# LedBlinker_End.net
KiCad netlist of a schematic drawn in Altium Designer
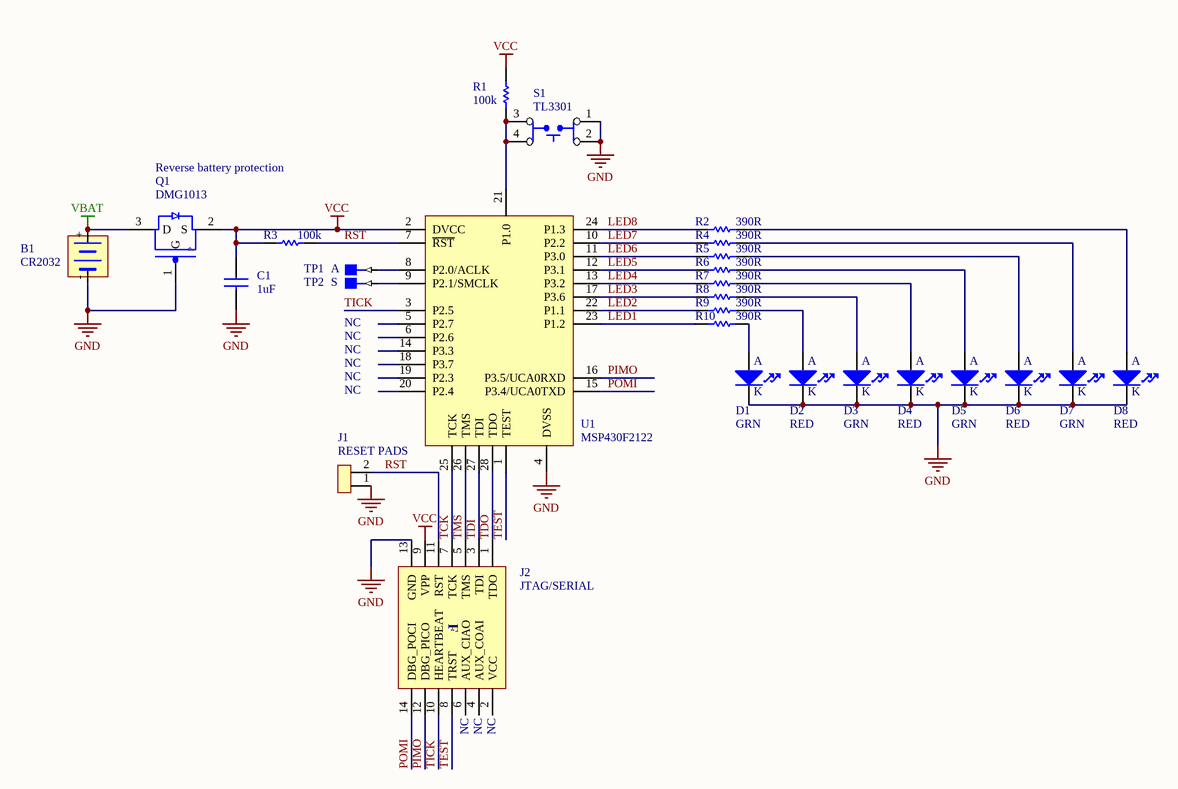
[diagram p0: LedBlinker End.SchDoc]

(export (version "E")
  (design (tool "Eeschema 10.0.6"))
  (components
    (comp (ref "B1")
      (value "CR2032")
      (footprint "CONN BATTERY HOLDER CR2032")
      (description "3V Coincell Battery")
      (fields
        (field (name "3. MANUFACTURER PART NUMBER") "BK-912")
        (field (name "4. DIGI-KEY PART NUMBER") "BK-912-ND")
        (field (name "7. MODIFIED BY") "JRL")
      )
      (libsource (lib "Altium Example Master Schematic Library End") (part "CONN BATTERY HOLDER CR2032"))
    )
    (comp (ref "C1")
      (value "1uF")
      (footprint "0603")
      (fields
        (field (name "5. INTERNAL PART NUMBER") "100009")
        (field (name "4. DIGI-KEY PART NUMBER") "587-1251-2-ND")
        (field (name "3. MANUFACTURER PART NUMBER") "EMK107BJ105KA-T")
        (field (name "7. MODIFIED BY") "JRL")
      )
      (libsource (lib "Altium Example Master Schematic Library End") (part "CAPACITOR NON-POLARIZED"))
    )
    (comp (ref "D1")
      (value "GRN")
      (footprint "PLCC-2 AK")
      (fields
        (field (name "3. MANUFACTURER PART NUMBER") "AA3528CGSK")
        (field (name "4. DIGI-KEY PART NUMBER") "754-1528-2-ND")
        (field (name "5. INTERNAL PART NUMBER") "100110")
        (field (name "7. MODIFIED BY") "JRL")
      )
      (libsource (lib "Altium Example Master Schematic Library End") (part "LED AK"))
    )
    (comp (ref "D2")
      (value "RED")
      (footprint "PLCC-2 AK")
      (fields
        (field (name "3. MANUFACTURER PART NUMBER") "AA3528SURSK")
        (field (name "4. DIGI-KEY PART NUMBER") "754-1537-2-ND")
        (field (name "5. INTERNAL PART NUMBER") "100113")
        (field (name "7. MODIFIED BY") "JRL")
      )
      (libsource (lib "Altium Example Master Schematic Library End") (part "LED AK"))
    )
    (comp (ref "D3")
      (value "GRN")
      (footprint "PLCC-2 AK")
      (fields
        (field (name "3. MANUFACTURER PART NUMBER") "AA3528CGSK")
        (field (name "4. DIGI-KEY PART NUMBER") "754-1528-2-ND")
        (field (name "5. INTERNAL PART NUMBER") "100110")
        (field (name "7. MODIFIED BY") "JRL")
      )
      (libsource (lib "Altium Example Master Schematic Library End") (part "LED AK"))
    )
    (comp (ref "D4")
      (value "RED")
      (footprint "PLCC-2 AK")
      (fields
        (field (name "3. MANUFACTURER PART NUMBER") "AA3528SURSK")
        (field (name "4. DIGI-KEY PART NUMBER") "754-1537-2-ND")
        (field (name "5. INTERNAL PART NUMBER") "100113")
        (field (name "7. MODIFIED BY") "JRL")
      )
      (libsource (lib "Altium Example Master Schematic Library End") (part "LED AK"))
    )
    (comp (ref "D5")
      (value "GRN")
      (footprint "PLCC-2 AK")
      (fields
        (field (name "3. MANUFACTURER PART NUMBER") "AA3528CGSK")
        (field (name "4. DIGI-KEY PART NUMBER") "754-1528-2-ND")
        (field (name "5. INTERNAL PART NUMBER") "100110")
        (field (name "7. MODIFIED BY") "JRL")
      )
      (libsource (lib "Altium Example Master Schematic Library End") (part "LED AK"))
    )
    (comp (ref "D6")
      (value "RED")
      (footprint "PLCC-2 AK")
      (fields
        (field (name "3. MANUFACTURER PART NUMBER") "AA3528SURSK")
        (field (name "4. DIGI-KEY PART NUMBER") "754-1537-2-ND")
        (field (name "5. INTERNAL PART NUMBER") "100113")
        (field (name "7. MODIFIED BY") "JRL")
      )
      (libsource (lib "Altium Example Master Schematic Library End") (part "LED AK"))
    )
    (comp (ref "D7")
      (value "GRN")
      (footprint "PLCC-2 AK")
      (fields
        (field (name "3. MANUFACTURER PART NUMBER") "AA3528CGSK")
        (field (name "4. DIGI-KEY PART NUMBER") "754-1528-2-ND")
        (field (name "5. INTERNAL PART NUMBER") "100110")
        (field (name "7. MODIFIED BY") "JRL")
      )
      (libsource (lib "Altium Example Master Schematic Library End") (part "LED AK"))
    )
    (comp (ref "D8")
      (value "RED")
      (footprint "PLCC-2 AK")
      (fields
        (field (name "3. MANUFACTURER PART NUMBER") "AA3528SURSK")
        (field (name "4. DIGI-KEY PART NUMBER") "754-1537-2-ND")
        (field (name "5. INTERNAL PART NUMBER") "100113")
        (field (name "7. MODIFIED BY") "JRL")
      )
      (libsource (lib "Altium Example Master Schematic Library End") (part "LED AK"))
    )
    (comp (ref "J1")
      (value "RESET PADS")
      (footprint "JUMPER POINTS")
      (fields (field (name "7. MODIFIED BY") "*"))
      (libsource (lib "Altium Example Master Schematic Library End") (part "CONN SIP 2"))
    )
    (comp (ref "J2")
      (value "JTAG/SERIAL")
      (footprint "CONN 14POS 7X2 SMT FEMALE SMALL")
      (fields
        (field (name "3. MANUFACTURER PART NUMBER") "20021321-00014T4LF")
        (field (name "4. DIGI-KEY PART NUMBER") "609-3771-ND")
        (field (name "5. INTERNAL PART NUMBER") "100254")
        (field (name "7. MODIFIED BY") "JRL")
      )
      (libsource (lib "Engenuics Master Schematic Library") (part "CONN JTAG/SERIAL DEBUG 14POS FEMALE"))
    )
    (comp (ref "Q1")
      (value "DMG1013")
      (footprint "SC-70-3")
      (fields
        (field (name "3. MANUFACTURER PART NUMBER") "DMG1013UW-7")
        (field (name "4. DIGI-KEY PART NUMBER") "DMG1013UW-7DICT-ND")
        (field (name "5. INTERNAL PART NUMBER") "100279")
        (field (name "7. MODIFIED BY") "JRL")
      )
      (libsource (lib "Altium Example Master Schematic Library End") (part "TRANS PMOS 1G 2S 3D"))
    )
    (comp (ref "R1")
      (value "100k")
      (footprint "0603")
      (fields
        (field (name "5. INTERNAL PART NUMBER") "100078")
        (field (name "4. DIGI-KEY PART NUMBER") "311-100KHRTR-ND")
        (field (name "3. MANUFACTURER PART NUMBER") "RC0603FR-07100KL")
        (field (name "7. MODIFIED BY") "JRL")
      )
      (libsource (lib "Altium Example Master Schematic Library End") (part "RESISTOR"))
    )
    (comp (ref "R2")
      (value "390R")
      (footprint "0603")
      (fields
        (field (name "5. INTERNAL PART NUMBER") "100098")
        (field (name "4. DIGI-KEY PART NUMBER") "311-390HRTR-ND")
        (field (name "3. MANUFACTURER PART NUMBER") "RC0603FR-07390RL")
        (field (name "7. MODIFIED BY") "JRL")
      )
      (libsource (lib "Altium Example Master Schematic Library End") (part "RESISTOR"))
    )
    (comp (ref "R3")
      (value "100k")
      (footprint "0603")
      (fields
        (field (name "5. INTERNAL PART NUMBER") "100078")
        (field (name "4. DIGI-KEY PART NUMBER") "311-100KHRTR-ND")
        (field (name "3. MANUFACTURER PART NUMBER") "RC0603FR-07100KL")
        (field (name "7. MODIFIED BY") "JRL")
      )
      (libsource (lib "Altium Example Master Schematic Library End") (part "RESISTOR"))
    )
    (comp (ref "R4")
      (value "390R")
      (footprint "0603")
      (fields
        (field (name "5. INTERNAL PART NUMBER") "100098")
        (field (name "4. DIGI-KEY PART NUMBER") "311-390HRTR-ND")
        (field (name "3. MANUFACTURER PART NUMBER") "RC0603FR-07390RL")
        (field (name "7. MODIFIED BY") "JRL")
      )
      (libsource (lib "Altium Example Master Schematic Library End") (part "RESISTOR"))
    )
    (comp (ref "R5")
      (value "390R")
      (footprint "0603")
      (fields
        (field (name "5. INTERNAL PART NUMBER") "100098")
        (field (name "4. DIGI-KEY PART NUMBER") "311-390HRTR-ND")
        (field (name "3. MANUFACTURER PART NUMBER") "RC0603FR-07390RL")
        (field (name "7. MODIFIED BY") "JRL")
      )
      (libsource (lib "Altium Example Master Schematic Library End") (part "RESISTOR"))
    )
    (comp (ref "R6")
      (value "390R")
      (footprint "0603")
      (fields
        (field (name "5. INTERNAL PART NUMBER") "100098")
        (field (name "4. DIGI-KEY PART NUMBER") "311-390HRTR-ND")
        (field (name "3. MANUFACTURER PART NUMBER") "RC0603FR-07390RL")
        (field (name "7. MODIFIED BY") "JRL")
      )
      (libsource (lib "Altium Example Master Schematic Library End") (part "RESISTOR"))
    )
    (comp (ref "R7")
      (value "390R")
      (footprint "0603")
      (fields
        (field (name "5. INTERNAL PART NUMBER") "100098")
        (field (name "4. DIGI-KEY PART NUMBER") "311-390HRTR-ND")
        (field (name "3. MANUFACTURER PART NUMBER") "RC0603FR-07390RL")
        (field (name "7. MODIFIED BY") "JRL")
      )
      (libsource (lib "Altium Example Master Schematic Library End") (part "RESISTOR"))
    )
    (comp (ref "R8")
      (value "390R")
      (footprint "0603")
      (fields
        (field (name "5. INTERNAL PART NUMBER") "100098")
        (field (name "4. DIGI-KEY PART NUMBER") "311-390HRTR-ND")
        (field (name "3. MANUFACTURER PART NUMBER") "RC0603FR-07390RL")
        (field (name "7. MODIFIED BY") "JRL")
      )
      (libsource (lib "Altium Example Master Schematic Library End") (part "RESISTOR"))
    )
    (comp (ref "R9")
      (value "390R")
      (footprint "0603")
      (fields
        (field (name "5. INTERNAL PART NUMBER") "100098")
        (field (name "4. DIGI-KEY PART NUMBER") "311-390HRTR-ND")
        (field (name "3. MANUFACTURER PART NUMBER") "RC0603FR-07390RL")
        (field (name "7. MODIFIED BY") "JRL")
      )
      (libsource (lib "Altium Example Master Schematic Library End") (part "RESISTOR"))
    )
    (comp (ref "R10")
      (value "390R")
      (footprint "0603")
      (fields
        (field (name "5. INTERNAL PART NUMBER") "100098")
        (field (name "4. DIGI-KEY PART NUMBER") "311-390HRTR-ND")
        (field (name "3. MANUFACTURER PART NUMBER") "RC0603FR-07390RL")
        (field (name "7. MODIFIED BY") "JRL")
      )
      (libsource (lib "Altium Example Master Schematic Library End") (part "RESISTOR"))
    )
    (comp (ref "S1")
      (value "TL3301")
      (footprint "SWITCH TACT SMT TL3301 J LEAD")
      (description "SPST TACT SWITCH")
      (fields
        (field (name "3. MANUFACTURER PART NUMBER") "TL3301AF160QJ")
        (field (name "4. DIGI-KEY PART NUMBER") "EG4374TR-ND")
        (field (name "7. MODIFIED BY") "JRL")
      )
      (libsource (lib "Engenuics Master Schematic Library") (part "SWITCH SPST TL3301 JLEAD"))
    )
    (comp (ref "TP1")
      (value "A")
      (footprint "TEST POINT SMT TINY")
      (fields (field (name "7. MODIFIED BY") "JRL"))
      (libsource (lib "Engenuics Master Schematic Library") (part "TEST POINT SMT"))
    )
    (comp (ref "TP2")
      (value "S")
      (footprint "TEST POINT SMT TINY")
      (fields (field (name "7. MODIFIED BY") "JRL"))
      (libsource (lib "Engenuics Master Schematic Library") (part "TEST POINT SMT"))
    )
    (comp (ref "U1")
      (value "MSP430F2122")
      (footprint "TSSOP28")
      (fields
        (field (name "3. MANUFACTURER PART NUMBER") "MSP430F2122IIPW")
        (field (name "4. DIGI-KEY PART NUMBER") "296-23363-2-ND")
        (field (name "5. INTERNAL PART NUMBER") "100207")
        (field (name "7. MODIFIED BY") "JRL")
      )
      (libsource (lib "Altium Example Master Schematic Library End") (part "MCU MSP430F2122 TSSOP28 LED BLINKER"))
    )
  )
  (nets
    (net (code "1") (name "/LED1") (class "Default")
      (node (ref "R10") (pin "1") (pinfunction "1_1") (pintype "passive"))
      (node (ref "U1") (pin "23") (pinfunction "P1.2_23") (pintype "passive"))
    )
    (net (code "2") (name "/LED2") (class "Default")
      (node (ref "R9") (pin "1") (pinfunction "1_1") (pintype "passive"))
      (node (ref "U1") (pin "22") (pinfunction "P1.1_22") (pintype "passive"))
    )
    (net (code "3") (name "/LED3") (class "Default")
      (node (ref "R8") (pin "1") (pinfunction "1_1") (pintype "passive"))
      (node (ref "U1") (pin "17") (pinfunction "P3.6_17") (pintype "passive"))
    )
    (net (code "4") (name "/LED4") (class "Default")
      (node (ref "R7") (pin "1") (pinfunction "1_1") (pintype "passive"))
      (node (ref "U1") (pin "13") (pinfunction "P3.2_13") (pintype "passive"))
    )
    (net (code "5") (name "/LED5") (class "Default")
      (node (ref "R6") (pin "1") (pinfunction "1_1") (pintype "passive"))
      (node (ref "U1") (pin "12") (pinfunction "P3.1_12") (pintype "passive"))
    )
    (net (code "6") (name "/LED6") (class "Default")
      (node (ref "R5") (pin "1") (pinfunction "1_1") (pintype "passive"))
      (node (ref "U1") (pin "11") (pinfunction "P3.0_11") (pintype "passive"))
    )
    (net (code "7") (name "/LED7") (class "Default")
      (node (ref "R4") (pin "1") (pinfunction "1_1") (pintype "passive"))
      (node (ref "U1") (pin "10") (pinfunction "P2.2_10") (pintype "passive"))
    )
    (net (code "8") (name "/LED8") (class "Default")
      (node (ref "R2") (pin "1") (pinfunction "1_1") (pintype "passive"))
      (node (ref "U1") (pin "24") (pinfunction "P1.3_24") (pintype "passive"))
    )
    (net (code "9") (name "/PIMO") (class "Default")
      (node (ref "J2") (pin "12") (pinfunction "DBG_PICO_12") (pintype "passive"))
      (node (ref "U1") (pin "16") (pinfunction "P3.5/UCA0RXD_16") (pintype "passive"))
    )
    (net (code "10") (name "/POMI") (class "Default")
      (node (ref "J2") (pin "14") (pinfunction "DBG_POCI_14") (pintype "passive"))
      (node (ref "U1") (pin "15") (pinfunction "P3.4/UCA0TXD_15") (pintype "passive"))
    )
    (net (code "11") (name "/RST") (class "Default")
      (node (ref "J1") (pin "2") (pintype "passive"))
      (node (ref "J2") (pin "11") (pinfunction "RST_11") (pintype "passive"))
      (node (ref "R3") (pin "1") (pinfunction "1_1") (pintype "passive"))
      (node (ref "U1") (pin "7") (pinfunction "~{RST}_7") (pintype "passive"))
    )
    (net (code "12") (name "/TCK") (class "Default")
      (node (ref "J2") (pin "7") (pinfunction "TCK_7") (pintype "passive"))
      (node (ref "U1") (pin "25") (pinfunction "TCK_25") (pintype "passive"))
    )
    (net (code "13") (name "/TDI") (class "Default")
      (node (ref "J2") (pin "3") (pinfunction "TDI_3") (pintype "passive"))
      (node (ref "U1") (pin "27") (pinfunction "TDI_27") (pintype "passive"))
    )
    (net (code "14") (name "/TDO") (class "Default")
      (node (ref "J2") (pin "1") (pinfunction "TDO_1") (pintype "passive"))
      (node (ref "U1") (pin "28") (pinfunction "TDO_28") (pintype "passive"))
    )
    (net (code "15") (name "/TEST") (class "Default")
      (node (ref "J2") (pin "8") (pinfunction "TRST_8") (pintype "passive"))
      (node (ref "U1") (pin "1") (pinfunction "TEST_1") (pintype "passive"))
    )
    (net (code "16") (name "/TICK") (class "Default")
      (node (ref "J2") (pin "10") (pinfunction "HEARTBEAT_10") (pintype "passive"))
      (node (ref "U1") (pin "3") (pinfunction "P2.5_3") (pintype "passive"))
    )
    (net (code "17") (name "/TMS") (class "Default")
      (node (ref "J2") (pin "5") (pinfunction "TMS_5") (pintype "passive"))
      (node (ref "U1") (pin "26") (pinfunction "TMS_26") (pintype "passive"))
    )
    (net (code "18") (name "GND") (class "Default")
      (node (ref "B1") (pin "-") (pintype "passive"))
      (node (ref "C1") (pin "2") (pinfunction "2_2") (pintype "passive"))
      (node (ref "D1") (pin "K") (pinfunction "K_K") (pintype "passive"))
      (node (ref "D2") (pin "K") (pinfunction "K_K") (pintype "passive"))
      (node (ref "D3") (pin "K") (pinfunction "K_K") (pintype "passive"))
      (node (ref "D4") (pin "K") (pinfunction "K_K") (pintype "passive"))
      (node (ref "D5") (pin "K") (pinfunction "K_K") (pintype "passive"))
      (node (ref "D6") (pin "K") (pinfunction "K_K") (pintype "passive"))
      (node (ref "D7") (pin "K") (pinfunction "K_K") (pintype "passive"))
      (node (ref "D8") (pin "K") (pinfunction "K_K") (pintype "passive"))
      (node (ref "J1") (pin "1") (pintype "passive"))
      (node (ref "J2") (pin "13") (pinfunction "GND_13") (pintype "power_in"))
      (node (ref "Q1") (pin "1") (pinfunction "G_1") (pintype "passive"))
      (node (ref "S1") (pin "1") (pinfunction "X1_1") (pintype "passive"))
      (node (ref "S1") (pin "2") (pinfunction "X2_2") (pintype "passive"))
      (node (ref "U1") (pin "4") (pinfunction "DVSS_4") (pintype "passive"))
    )
    (net (code "19") (name "Net-(D1-PadA)") (class "Default")
      (node (ref "D1") (pin "A") (pinfunction "A_A") (pintype "passive"))
      (node (ref "R10") (pin "2") (pinfunction "2_2") (pintype "passive"))
    )
    (net (code "20") (name "Net-(D2-PadA)") (class "Default")
      (node (ref "D2") (pin "A") (pinfunction "A_A") (pintype "passive"))
      (node (ref "R9") (pin "2") (pinfunction "2_2") (pintype "passive"))
    )
    (net (code "21") (name "Net-(D3-PadA)") (class "Default")
      (node (ref "D3") (pin "A") (pinfunction "A_A") (pintype "passive"))
      (node (ref "R8") (pin "2") (pinfunction "2_2") (pintype "passive"))
    )
    (net (code "22") (name "Net-(D4-PadA)") (class "Default")
      (node (ref "D4") (pin "A") (pinfunction "A_A") (pintype "passive"))
      (node (ref "R7") (pin "2") (pinfunction "2_2") (pintype "passive"))
    )
    (net (code "23") (name "Net-(D5-PadA)") (class "Default")
      (node (ref "D5") (pin "A") (pinfunction "A_A") (pintype "passive"))
      (node (ref "R6") (pin "2") (pinfunction "2_2") (pintype "passive"))
    )
    (net (code "24") (name "Net-(D6-PadA)") (class "Default")
      (node (ref "D6") (pin "A") (pinfunction "A_A") (pintype "passive"))
      (node (ref "R5") (pin "2") (pinfunction "2_2") (pintype "passive"))
    )
    (net (code "25") (name "Net-(D7-PadA)") (class "Default")
      (node (ref "D7") (pin "A") (pinfunction "A_A") (pintype "passive"))
      (node (ref "R4") (pin "2") (pinfunction "2_2") (pintype "passive"))
    )
    (net (code "26") (name "Net-(D8-PadA)") (class "Default")
      (node (ref "D8") (pin "A") (pinfunction "A_A") (pintype "passive"))
      (node (ref "R2") (pin "2") (pinfunction "2_2") (pintype "passive"))
    )
    (net (code "27") (name "Net-(S1-Y1)") (class "Default")
      (node (ref "R1") (pin "1") (pinfunction "1_1") (pintype "passive"))
      (node (ref "S1") (pin "3") (pinfunction "Y1_3") (pintype "passive"))
      (node (ref "S1") (pin "4") (pinfunction "Y2_4") (pintype "passive"))
      (node (ref "U1") (pin "21") (pinfunction "P1.0_21") (pintype "passive"))
    )
    (net (code "28") (name "Net-(U1-P2.0{slash}ACLK)") (class "Default")
      (node (ref "TP1") (pin "1") (pinfunction "1_1") (pintype "input"))
      (node (ref "U1") (pin "8") (pinfunction "P2.0/ACLK_8") (pintype "passive"))
    )
    (net (code "29") (name "Net-(U1-P2.1{slash}SMCLK)") (class "Default")
      (node (ref "TP2") (pin "1") (pinfunction "1_1") (pintype "input"))
      (node (ref "U1") (pin "9") (pinfunction "P2.1/SMCLK_9") (pintype "passive"))
    )
    (net (code "30") (name "VBAT") (class "Default")
      (node (ref "B1") (pin "+") (pintype "passive"))
      (node (ref "Q1") (pin "3") (pinfunction "D_3") (pintype "passive"))
    )
    (net (code "31") (name "VCC") (class "Default")
      (node (ref "C1") (pin "1") (pinfunction "1_1") (pintype "passive"))
      (node (ref "J2") (pin "9") (pinfunction "VPP_9") (pintype "passive"))
      (node (ref "Q1") (pin "2") (pinfunction "S_2") (pintype "passive"))
      (node (ref "R1") (pin "2") (pinfunction "2_2") (pintype "passive"))
      (node (ref "R3") (pin "2") (pinfunction "2_2") (pintype "passive"))
      (node (ref "U1") (pin "2") (pinfunction "DVCC_2") (pintype "passive"))
    )
    (net (code "32") (name "unconnected-(J2-AUX_CIAO-Pad6)") (class "Default")
      (node (ref "J2") (pin "6") (pinfunction "AUX_CIAO_6") (pintype "passive"))
    )
    (net (code "33") (name "unconnected-(J2-AUX_COAI-Pad4)") (class "Default")
      (node (ref "J2") (pin "4") (pinfunction "AUX_COAI_4") (pintype "passive"))
    )
    (net (code "34") (name "unconnected-(J2-VCC-Pad2)") (class "Default")
      (node (ref "J2") (pin "2") (pinfunction "VCC_2") (pintype "passive"))
    )
    (net (code "35") (name "unconnected-(U1-P2.3-Pad19)") (class "Default")
      (node (ref "U1") (pin "19") (pinfunction "P2.3_19") (pintype "passive"))
    )
    (net (code "36") (name "unconnected-(U1-P2.4-Pad20)") (class "Default")
      (node (ref "U1") (pin "20") (pinfunction "P2.4_20") (pintype "passive"))
    )
    (net (code "37") (name "unconnected-(U1-P2.6-Pad6)") (class "Default")
      (node (ref "U1") (pin "6") (pinfunction "P2.6_6") (pintype "passive"))
    )
    (net (code "38") (name "unconnected-(U1-P2.7-Pad5)") (class "Default")
      (node (ref "U1") (pin "5") (pinfunction "P2.7_5") (pintype "passive"))
    )
    (net (code "39") (name "unconnected-(U1-P3.3-Pad14)") (class "Default")
      (node (ref "U1") (pin "14") (pinfunction "P3.3_14") (pintype "passive"))
    )
    (net (code "40") (name "unconnected-(U1-P3.7-Pad18)") (class "Default")
      (node (ref "U1") (pin "18") (pinfunction "P3.7_18") (pintype "passive"))
    )
  )
)
